# 1.net
KiCad netlist of a schematic drawn in EAGLE
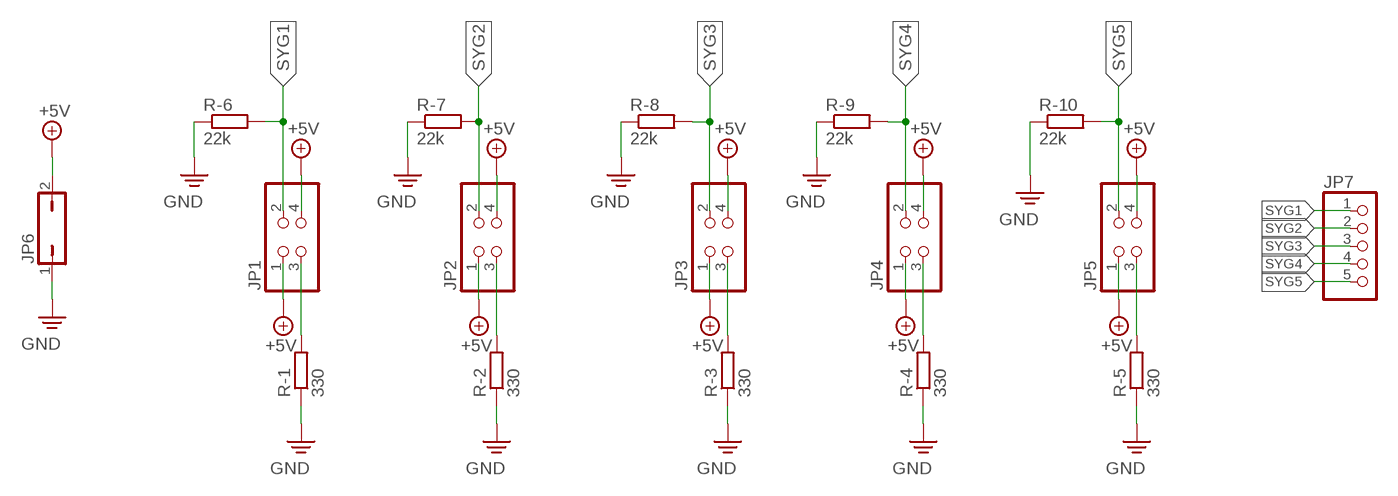
[diagram p0: schematic, sheet 1]

(export (version "E")
  (design (tool "Eeschema 10.0.6"))
  (components
    (comp (ref "JP1")
      (value "PINHD-2X2")
      (footprint "eagle-import:2X02")
      (libsource (lib "eagle-import") (part "PINHD-2X2"))
    )
    (comp (ref "JP2")
      (value "PINHD-2X2")
      (footprint "eagle-import:2X02")
      (libsource (lib "eagle-import") (part "PINHD-2X2"))
    )
    (comp (ref "JP3")
      (value "PINHD-2X2")
      (footprint "eagle-import:2X02")
      (libsource (lib "eagle-import") (part "PINHD-2X2"))
    )
    (comp (ref "JP4")
      (value "PINHD-2X2")
      (footprint "eagle-import:2X02")
      (libsource (lib "eagle-import") (part "PINHD-2X2"))
    )
    (comp (ref "JP5")
      (value "PINHD-2X2")
      (footprint "eagle-import:2X02")
      (libsource (lib "eagle-import") (part "PINHD-2X2"))
    )
    (comp (ref "JP6")
      (value "JP1Q")
      (footprint "eagle-import:JP1")
      (libsource (lib "eagle-import") (part "JP1Q"))
    )
    (comp (ref "JP7")
      (value "PINHD-1X5")
      (footprint "eagle-import:1X05")
      (libsource (lib "eagle-import") (part "PINHD-1X5"))
    )
    (comp (ref "R-1")
      (value "330")
      (footprint "eagle-import:0204_7")
      (libsource (lib "eagle-import") (part "R-EU_0204/7"))
    )
    (comp (ref "R-2")
      (value "330")
      (footprint "eagle-import:0204_7")
      (libsource (lib "eagle-import") (part "R-EU_0204/7"))
    )
    (comp (ref "R-3")
      (value "330")
      (footprint "eagle-import:0204_7")
      (libsource (lib "eagle-import") (part "R-EU_0204/7"))
    )
    (comp (ref "R-4")
      (value "330")
      (footprint "eagle-import:0204_7")
      (libsource (lib "eagle-import") (part "R-EU_0204/7"))
    )
    (comp (ref "R-5")
      (value "330")
      (footprint "eagle-import:0204_7")
      (libsource (lib "eagle-import") (part "R-EU_0204/7"))
    )
    (comp (ref "R-6")
      (value "22k")
      (footprint "eagle-import:0204_7")
      (libsource (lib "eagle-import") (part "R-EU_0204/7"))
    )
    (comp (ref "R-7")
      (value "22k")
      (footprint "eagle-import:0204_7")
      (libsource (lib "eagle-import") (part "R-EU_0204/7"))
    )
    (comp (ref "R-8")
      (value "22k")
      (footprint "eagle-import:0204_7")
      (libsource (lib "eagle-import") (part "R-EU_0204/7"))
    )
    (comp (ref "R-9")
      (value "22k")
      (footprint "eagle-import:0204_7")
      (libsource (lib "eagle-import") (part "R-EU_0204/7"))
    )
    (comp (ref "R-10")
      (value "22k")
      (footprint "eagle-import:0204_7")
      (libsource (lib "eagle-import") (part "R-EU_0204/7"))
    )
  )
  (nets
    (net (code "1") (name "+5V") (class "Default")
      (node (ref "JP1") (pin "1") (pinfunction "1_1") (pintype "passive"))
      (node (ref "JP1") (pin "4") (pinfunction "4_4") (pintype "passive"))
      (node (ref "JP2") (pin "1") (pinfunction "1_1") (pintype "passive"))
      (node (ref "JP2") (pin "4") (pinfunction "4_4") (pintype "passive"))
      (node (ref "JP3") (pin "1") (pinfunction "1_1") (pintype "passive"))
      (node (ref "JP3") (pin "4") (pinfunction "4_4") (pintype "passive"))
      (node (ref "JP4") (pin "1") (pinfunction "1_1") (pintype "passive"))
      (node (ref "JP4") (pin "4") (pinfunction "4_4") (pintype "passive"))
      (node (ref "JP5") (pin "1") (pinfunction "1_1") (pintype "passive"))
      (node (ref "JP5") (pin "4") (pinfunction "4_4") (pintype "passive"))
      (node (ref "JP6") (pin "2") (pinfunction "2_2") (pintype "passive"))
    )
    (net (code "2") (name "GND") (class "Default")
      (node (ref "JP6") (pin "1") (pinfunction "1_1") (pintype "passive"))
      (node (ref "R-1") (pin "1") (pinfunction "1_1") (pintype "passive"))
      (node (ref "R-10") (pin "1") (pinfunction "1_1") (pintype "passive"))
      (node (ref "R-2") (pin "1") (pinfunction "1_1") (pintype "passive"))
      (node (ref "R-3") (pin "1") (pinfunction "1_1") (pintype "passive"))
      (node (ref "R-4") (pin "1") (pinfunction "1_1") (pintype "passive"))
      (node (ref "R-5") (pin "1") (pinfunction "1_1") (pintype "passive"))
      (node (ref "R-6") (pin "1") (pinfunction "1_1") (pintype "passive"))
      (node (ref "R-7") (pin "1") (pinfunction "1_1") (pintype "passive"))
      (node (ref "R-8") (pin "1") (pinfunction "1_1") (pintype "passive"))
      (node (ref "R-9") (pin "1") (pinfunction "1_1") (pintype "passive"))
    )
    (net (code "3") (name "Net-(JP1-Pad3)") (class "Default")
      (node (ref "JP1") (pin "3") (pinfunction "3_3") (pintype "passive"))
      (node (ref "R-1") (pin "2") (pinfunction "2_2") (pintype "passive"))
    )
    (net (code "4") (name "Net-(JP2-Pad3)") (class "Default")
      (node (ref "JP2") (pin "3") (pinfunction "3_3") (pintype "passive"))
      (node (ref "R-2") (pin "2") (pinfunction "2_2") (pintype "passive"))
    )
    (net (code "5") (name "Net-(JP3-Pad3)") (class "Default")
      (node (ref "JP3") (pin "3") (pinfunction "3_3") (pintype "passive"))
      (node (ref "R-3") (pin "2") (pinfunction "2_2") (pintype "passive"))
    )
    (net (code "6") (name "Net-(JP4-Pad3)") (class "Default")
      (node (ref "JP4") (pin "3") (pinfunction "3_3") (pintype "passive"))
      (node (ref "R-4") (pin "2") (pinfunction "2_2") (pintype "passive"))
    )
    (net (code "7") (name "Net-(JP5-Pad3)") (class "Default")
      (node (ref "JP5") (pin "3") (pinfunction "3_3") (pintype "passive"))
      (node (ref "R-5") (pin "2") (pinfunction "2_2") (pintype "passive"))
    )
    (net (code "8") (name "SYG1") (class "Default")
      (node (ref "JP1") (pin "2") (pinfunction "2_2") (pintype "passive"))
      (node (ref "JP7") (pin "1") (pinfunction "1_1") (pintype "passive"))
      (node (ref "R-6") (pin "2") (pinfunction "2_2") (pintype "passive"))
    )
    (net (code "9") (name "SYG2") (class "Default")
      (node (ref "JP2") (pin "2") (pinfunction "2_2") (pintype "passive"))
      (node (ref "JP7") (pin "2") (pinfunction "2_2") (pintype "passive"))
      (node (ref "R-7") (pin "2") (pinfunction "2_2") (pintype "passive"))
    )
    (net (code "10") (name "SYG3") (class "Default")
      (node (ref "JP3") (pin "2") (pinfunction "2_2") (pintype "passive"))
      (node (ref "JP7") (pin "3") (pinfunction "3_3") (pintype "passive"))
      (node (ref "R-8") (pin "2") (pinfunction "2_2") (pintype "passive"))
    )
    (net (code "11") (name "SYG4") (class "Default")
      (node (ref "JP4") (pin "2") (pinfunction "2_2") (pintype "passive"))
      (node (ref "JP7") (pin "4") (pinfunction "4_4") (pintype "passive"))
      (node (ref "R-9") (pin "2") (pinfunction "2_2") (pintype "passive"))
    )
    (net (code "12") (name "SYG5") (class "Default")
      (node (ref "JP5") (pin "2") (pinfunction "2_2") (pintype "passive"))
      (node (ref "JP7") (pin "5") (pinfunction "5_5") (pintype "passive"))
      (node (ref "R-10") (pin "2") (pinfunction "2_2") (pintype "passive"))
    )
  )
)
